# main_board_v2.net
KiCad netlist of a schematic drawn in EAGLE
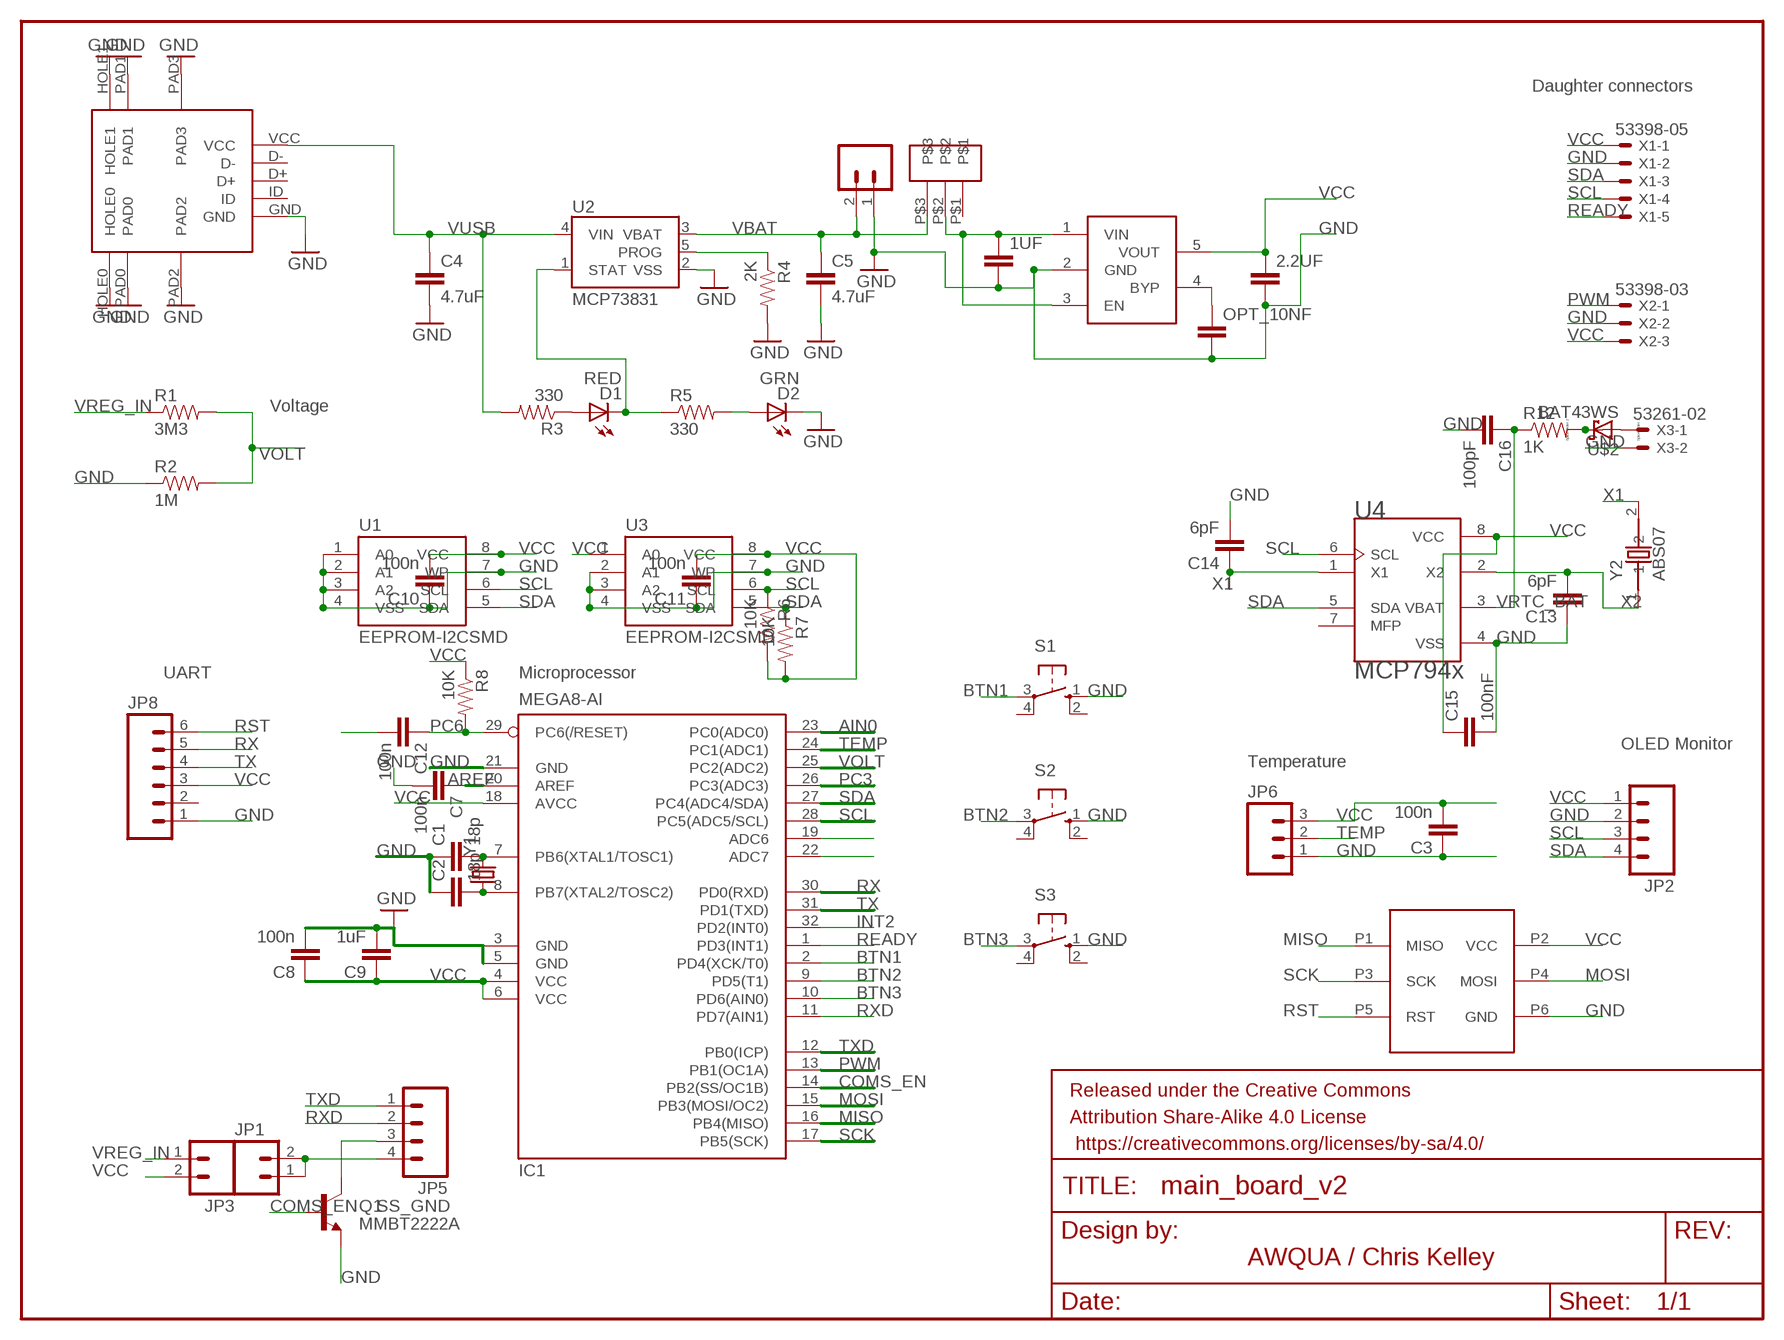
[diagram p0: schematic, sheet 1]

(export (version "E")
  (design (tool "Eeschema 10.0.6"))
  (components
    (comp (ref "1UF")
      (value "CAP0603-CAP")
      (footprint "eagle-import:0603-CAP")
      (libsource (lib "eagle-import") (part "SparkFun-Passives_CAP0603-CAP"))
    )
    (comp (ref "2.2UF")
      (value "CAP0603-CAP")
      (footprint "eagle-import:0603-CAP")
      (libsource (lib "eagle-import") (part "SparkFun-Passives_CAP0603-CAP"))
    )
    (comp (ref "C1")
      (value "18p")
      (footprint "eagle-import:0603-CAP")
      (libsource (lib "eagle-import") (part "CAP0603-CAP"))
    )
    (comp (ref "C2")
      (value "18p")
      (footprint "eagle-import:0603-CAP")
      (libsource (lib "eagle-import") (part "CAP0603-CAP"))
    )
    (comp (ref "C3")
      (value "100n")
      (footprint "eagle-import:0603-CAP")
      (libsource (lib "eagle-import") (part "CAP0603-CAP"))
    )
    (comp (ref "C4")
      (value "4.7uF")
      (footprint "eagle-import:0402-CAP")
      (libsource (lib "eagle-import") (part "CAP0402-CAP"))
    )
    (comp (ref "C5")
      (value "4.7uF")
      (footprint "eagle-import:0402-CAP")
      (libsource (lib "eagle-import") (part "CAP0402-CAP"))
    )
    (comp (ref "C7")
      (value "100n")
      (footprint "eagle-import:0603-CAP")
      (libsource (lib "eagle-import") (part "CAP0603-CAP"))
    )
    (comp (ref "C8")
      (value "100n")
      (footprint "eagle-import:0603-CAP")
      (libsource (lib "eagle-import") (part "CAP0603-CAP"))
    )
    (comp (ref "C9")
      (value "1uF")
      (footprint "eagle-import:0603-CAP")
      (libsource (lib "eagle-import") (part "CAP0603-CAP"))
    )
    (comp (ref "C10")
      (value "100n")
      (footprint "eagle-import:0603-CAP")
      (libsource (lib "eagle-import") (part "CAP0603-CAP"))
    )
    (comp (ref "C11")
      (value "100n")
      (footprint "eagle-import:0603-CAP")
      (libsource (lib "eagle-import") (part "CAP0603-CAP"))
    )
    (comp (ref "C12")
      (value "100n")
      (footprint "eagle-import:0603-CAP")
      (libsource (lib "eagle-import") (part "CAP0603-CAP"))
    )
    (comp (ref "C13")
      (value "6pF")
      (footprint "eagle-import:0603-CAP")
      (libsource (lib "eagle-import") (part "SparkFun-Passives_CAP0603-CAP"))
    )
    (comp (ref "C14")
      (value "6pF")
      (footprint "eagle-import:0603-CAP")
      (libsource (lib "eagle-import") (part "SparkFun-Passives_CAP0603-CAP"))
    )
    (comp (ref "C15")
      (value "100nF")
      (footprint "eagle-import:0603-CAP")
      (libsource (lib "eagle-import") (part "SparkFun-Passives_CAP0603-CAP"))
    )
    (comp (ref "C16")
      (value "100pF")
      (footprint "eagle-import:0603-CAP")
      (libsource (lib "eagle-import") (part "SparkFun-Passives_CAP0603-CAP"))
    )
    (comp (ref "D1")
      (value "RED")
      (footprint "eagle-import:LED-0603")
      (libsource (lib "eagle-import") (part "LED0603"))
    )
    (comp (ref "D2")
      (value "GRN")
      (footprint "eagle-import:LED-0603")
      (libsource (lib "eagle-import") (part "LED0603"))
    )
    (comp (ref "FRAME1")
      (value "FRAME-LETTER")
      (footprint "eagle-import:CREATIVE_COMMONS")
      (libsource (lib "eagle-import") (part "FRAME-LETTER"))
    )
    (comp (ref "IC1")
      (value "MEGA8-AI")
      (footprint "eagle-import:TQFP32-08")
      (fields (field (name "MPN") "ATMEGA8-16AU"))
      (libsource (lib "eagle-import") (part "MEGA8-AI"))
    )
    (comp (ref "JP1")
      (value "M02PTH")
      (footprint "eagle-import:1X02")
      (libsource (lib "eagle-import") (part "SparkFun-Connectors_M02PTH"))
    )
    (comp (ref "JP2")
      (value "M04PTH")
      (footprint "eagle-import:1X04")
      (libsource (lib "eagle-import") (part "M04PTH"))
    )
    (comp (ref "JP3")
      (value "M02PTH")
      (footprint "eagle-import:1X02")
      (libsource (lib "eagle-import") (part "SparkFun-Connectors_M02PTH"))
    )
    (comp (ref "JP5")
      (value "M04PTH")
      (footprint "eagle-import:1X04")
      (libsource (lib "eagle-import") (part "M04PTH"))
    )
    (comp (ref "JP6")
      (value "M03PTH")
      (footprint "eagle-import:1X03")
      (libsource (lib "eagle-import") (part "M03PTH"))
    )
    (comp (ref "JP7")
      (value "LiPo Battery")
      (footprint "eagle-import:JST-2-SMD")
      (libsource (lib "eagle-import") (part "M02-JST-2MM-SMT"))
    )
    (comp (ref "JP8")
      (value "M06SILK_FEMALE_PTH")
      (footprint "eagle-import:1X06")
      (libsource (lib "eagle-import") (part "M06SILK_FEMALE_PTH"))
    )
    (comp (ref "OPT_10NF")
      (value "CAP0603-CAP")
      (footprint "eagle-import:0603-CAP")
      (libsource (lib "eagle-import") (part "SparkFun-Passives_CAP0603-CAP"))
    )
    (comp (ref "Q1")
      (value "MMBT2222A")
      (footprint "eagle-import:SOT23-3")
      (libsource (lib "eagle-import") (part "TRANSISTOR_NPNMMBT2222A"))
    )
    (comp (ref "R1")
      (value "3M3")
      (footprint "eagle-import:0603-RES")
      (libsource (lib "eagle-import") (part "RESISTOR0603"))
    )
    (comp (ref "R2")
      (value "1M")
      (footprint "eagle-import:0603-RES")
      (libsource (lib "eagle-import") (part "RESISTOR0603"))
    )
    (comp (ref "R3")
      (value "330")
      (footprint "eagle-import:0402-RES")
      (libsource (lib "eagle-import") (part "RESISTOR0402-RES"))
    )
    (comp (ref "R4")
      (value "2K")
      (footprint "eagle-import:0402-RES")
      (libsource (lib "eagle-import") (part "RESISTOR0402-RES"))
    )
    (comp (ref "R5")
      (value "330")
      (footprint "eagle-import:0402-RES")
      (libsource (lib "eagle-import") (part "RESISTOR0402-RES"))
    )
    (comp (ref "R6")
      (value "10K")
      (footprint "eagle-import:0603-RES")
      (libsource (lib "eagle-import") (part "RESISTOR0603-RES"))
    )
    (comp (ref "R7")
      (value "10K")
      (footprint "eagle-import:0603-RES")
      (libsource (lib "eagle-import") (part "RESISTOR0603-RES"))
    )
    (comp (ref "R8")
      (value "10K")
      (footprint "eagle-import:0402-RES")
      (libsource (lib "eagle-import") (part "RESISTOR0402-RES"))
    )
    (comp (ref "R12")
      (value "1K")
      (footprint "eagle-import:0603-RES")
      (libsource (lib "eagle-import") (part "SparkFun-Passives_RESISTOR0603-RES"))
    )
    (comp (ref "S1")
      (value "40-XX")
      (footprint "eagle-import:B3F-40XX")
      (fields (field (name "MF") "OMRON COMPONENTS USA") (field (name "MPN") "B3F-4000"))
      (libsource (lib "eagle-import") (part "40-XX"))
    )
    (comp (ref "S2")
      (value "40-XX")
      (footprint "eagle-import:B3F-40XX")
      (fields (field (name "MF") "OMRON COMPONENTS USA") (field (name "MPN") "B3F-4000"))
      (libsource (lib "eagle-import") (part "40-XX"))
    )
    (comp (ref "S3")
      (value "40-XX")
      (footprint "eagle-import:B3F-40XX")
      (fields (field (name "MF") "OMRON COMPONENTS USA") (field (name "MPN") "B3F-4000"))
      (libsource (lib "eagle-import") (part "40-XX"))
    )
    (comp (ref "U$1")
      (value "ISP-SMD-6PIN")
      (footprint "eagle-import:ISP-SMD-6PIN")
      (libsource (lib "eagle-import") (part "ISP-SMD-6PIN"))
    )
    (comp (ref "U$2")
      (value "BAT43WS")
      (footprint "eagle-import:BAT43WS")
      (libsource (lib "eagle-import") (part "BAT43WS"))
    )
    (comp (ref "U$3")
      (value "USBMICRO-10118193-0001LF")
      (footprint "eagle-import:USBMICRO-10118193-0001LF")
      (libsource (lib "eagle-import") (part "USBMICRO-10118193-0001LF"))
    )
    (comp (ref "U$6")
      (value "LP2985")
      (footprint "eagle-import:LP2985")
      (libsource (lib "eagle-import") (part "LP2985"))
    )
    (comp (ref "U$7")
      (value "OS102-SPDT-SWITCH")
      (footprint "eagle-import:OS102-SPDT-SWITCH")
      (libsource (lib "eagle-import") (part "OS102-SPDT-SWITCH"))
    )
    (comp (ref "U1")
      (value "EEPROM-I2CSMD")
      (footprint "eagle-import:SO08")
      (libsource (lib "eagle-import") (part "EEPROM-I2CSMD"))
    )
    (comp (ref "U2")
      (value "MCP73831")
      (footprint "eagle-import:SOT23-5")
      (libsource (lib "eagle-import") (part "MCP73831"))
    )
    (comp (ref "U3")
      (value "EEPROM-I2CSMD")
      (footprint "eagle-import:SO08")
      (libsource (lib "eagle-import") (part "EEPROM-I2CSMD"))
    )
    (comp (ref "U4")
      (value "MCP794x")
      (footprint "eagle-import:SOIC127P600X175-8N")
      (fields (field (name "MF") "Microchip") (field (name "MP") "MCP7940M-I/SN"))
      (libsource (lib "eagle-import") (part "MCP7940M-I/SN"))
    )
    (comp (ref "X1")
      (value "53398-05")
      (footprint "eagle-import:53398-05")
      (libsource (lib "eagle-import") (part "53?-05398"))
    )
    (comp (ref "X2")
      (value "53398-03")
      (footprint "eagle-import:53398-03")
      (libsource (lib "eagle-import") (part "53?-03398"))
    )
    (comp (ref "X3")
      (value "53261-02")
      (footprint "eagle-import:53261-02")
      (libsource (lib "eagle-import") (part "53?-02261"))
    )
    (comp (ref "Y1")
      (value "CRYSTAL5X3")
      (footprint "eagle-import:CRYSTAL-SMD-5X3")
      (libsource (lib "eagle-import") (part "CRYSTAL5X3"))
    )
    (comp (ref "Y2")
      (value "ABS07")
      (footprint "eagle-import:XTAL320X150X90")
      (fields (field (name "MF") "Abracon") (field (name "MP") "ABS07-32.768KHZ-T"))
      (libsource (lib "eagle-import") (part "ABS07-32.768KHZ-T"))
    )
  )
  (nets
    (net (code "1") (name "/AIN0") (class "Default")
      (node (ref "IC1") (pin "23") (pinfunction "PC0(ADC0)_23") (pintype "bidirectional"))
    )
    (net (code "2") (name "/AREF") (class "Default")
      (node (ref "C7") (pin "1") (pinfunction "1_1") (pintype "passive"))
      (node (ref "IC1") (pin "20") (pinfunction "AREF_20") (pintype "passive"))
    )
    (net (code "3") (name "/BTN1") (class "Default")
      (node (ref "IC1") (pin "2") (pinfunction "PD4(XCK/T0)_2") (pintype "bidirectional"))
      (node (ref "S1") (pin "3") (pinfunction "P_3") (pintype "passive"))
    )
    (net (code "4") (name "/BTN2") (class "Default")
      (node (ref "IC1") (pin "9") (pinfunction "PD5(T1)_9") (pintype "bidirectional"))
      (node (ref "S2") (pin "3") (pinfunction "P_3") (pintype "passive"))
    )
    (net (code "5") (name "/BTN3") (class "Default")
      (node (ref "IC1") (pin "10") (pinfunction "PD6(AIN0)_10") (pintype "bidirectional"))
      (node (ref "S3") (pin "3") (pinfunction "P_3") (pintype "passive"))
    )
    (net (code "6") (name "/COMS_EN") (class "Default")
      (node (ref "IC1") (pin "14") (pinfunction "PB2(SS/OC1B)_14") (pintype "bidirectional"))
      (node (ref "Q1") (pin "1") (pinfunction "B_1") (pintype "passive"))
    )
    (net (code "7") (name "/INT2") (class "Default")
      (node (ref "IC1") (pin "32") (pinfunction "PD2(INT0)_32") (pintype "bidirectional"))
    )
    (net (code "8") (name "/MISO") (class "Default")
      (node (ref "IC1") (pin "16") (pinfunction "PB4(MISO)_16") (pintype "bidirectional"))
      (node (ref "U$1") (pin "P1") (pinfunction "MISO_P1") (pintype "bidirectional"))
    )
    (net (code "9") (name "/MOSI") (class "Default")
      (node (ref "IC1") (pin "15") (pinfunction "PB3(MOSI/OC2)_15") (pintype "bidirectional"))
      (node (ref "U$1") (pin "P4") (pinfunction "MOSI_P4") (pintype "bidirectional"))
    )
    (net (code "10") (name "/PC3") (class "Default")
      (node (ref "IC1") (pin "26") (pinfunction "PC3(ADC3)_26") (pintype "bidirectional"))
    )
    (net (code "11") (name "/PC6") (class "Default")
      (node (ref "C12") (pin "1") (pinfunction "1_1") (pintype "passive"))
      (node (ref "IC1") (pin "29") (pinfunction "PC6(/RESET)_29") (pintype "bidirectional"))
      (node (ref "R8") (pin "2") (pinfunction "2_2") (pintype "passive"))
    )
    (net (code "12") (name "/PWM") (class "Default")
      (node (ref "IC1") (pin "13") (pinfunction "PB1(OC1A)_13") (pintype "bidirectional"))
      (node (ref "X2") (pin "1") (pinfunction "S_1") (pintype "passive"))
    )
    (net (code "13") (name "/READY") (class "Default")
      (node (ref "IC1") (pin "1") (pinfunction "PD3(INT1)_1") (pintype "bidirectional"))
      (node (ref "X1") (pin "5") (pinfunction "S_5") (pintype "passive"))
    )
    (net (code "14") (name "/RST") (class "Default")
      (node (ref "C12") (pin "2") (pinfunction "2_2") (pintype "passive"))
      (node (ref "JP8") (pin "6") (pinfunction "6_6") (pintype "passive"))
      (node (ref "U$1") (pin "P5") (pinfunction "RST_P5") (pintype "bidirectional"))
    )
    (net (code "15") (name "/RX") (class "Default")
      (node (ref "IC1") (pin "30") (pinfunction "PD0(RXD)_30") (pintype "bidirectional"))
      (node (ref "JP8") (pin "5") (pinfunction "5_5") (pintype "passive"))
    )
    (net (code "16") (name "/RXD") (class "Default")
      (node (ref "IC1") (pin "11") (pinfunction "PD7(AIN1)_11") (pintype "bidirectional"))
      (node (ref "JP5") (pin "2") (pinfunction "2_2") (pintype "passive"))
    )
    (net (code "17") (name "/SCK") (class "Default")
      (node (ref "IC1") (pin "17") (pinfunction "PB5(SCK)_17") (pintype "bidirectional"))
      (node (ref "U$1") (pin "P3") (pinfunction "SCK_P3") (pintype "bidirectional"))
    )
    (net (code "18") (name "/SCL") (class "Default")
      (node (ref "IC1") (pin "28") (pinfunction "PC5(ADC5/SCL)_28") (pintype "bidirectional"))
      (node (ref "JP2") (pin "3") (pinfunction "3_3") (pintype "passive"))
      (node (ref "R6") (pin "1") (pinfunction "1_1") (pintype "passive"))
      (node (ref "U1") (pin "6") (pinfunction "SCL_6") (pintype "bidirectional"))
      (node (ref "U3") (pin "6") (pinfunction "SCL_6") (pintype "bidirectional"))
      (node (ref "U4") (pin "6") (pinfunction "SCL_6") (pintype "input"))
      (node (ref "X1") (pin "4") (pinfunction "S_4") (pintype "passive"))
    )
    (net (code "19") (name "/SDA") (class "Default")
      (node (ref "IC1") (pin "27") (pinfunction "PC4(ADC4/SDA)_27") (pintype "bidirectional"))
      (node (ref "JP2") (pin "4") (pinfunction "4_4") (pintype "passive"))
      (node (ref "R7") (pin "1") (pinfunction "1_1") (pintype "passive"))
      (node (ref "U1") (pin "5") (pinfunction "SDA_5") (pintype "bidirectional"))
      (node (ref "U3") (pin "5") (pinfunction "SDA_5") (pintype "bidirectional"))
      (node (ref "U4") (pin "5") (pinfunction "SDA_5") (pintype "bidirectional"))
      (node (ref "X1") (pin "3") (pinfunction "S_3") (pintype "passive"))
    )
    (net (code "20") (name "/SS_GND") (class "Default")
      (node (ref "JP5") (pin "3") (pinfunction "3_3") (pintype "passive"))
      (node (ref "Q1") (pin "3") (pinfunction "C_3") (pintype "passive"))
    )
    (net (code "21") (name "/TEMP") (class "Default")
      (node (ref "IC1") (pin "24") (pinfunction "PC1(ADC1)_24") (pintype "bidirectional"))
      (node (ref "JP6") (pin "2") (pinfunction "2_2") (pintype "passive"))
    )
    (net (code "22") (name "/TX") (class "Default")
      (node (ref "IC1") (pin "31") (pinfunction "PD1(TXD)_31") (pintype "bidirectional"))
      (node (ref "JP8") (pin "4") (pinfunction "4_4") (pintype "passive"))
    )
    (net (code "23") (name "/TXD") (class "Default")
      (node (ref "IC1") (pin "12") (pinfunction "PB0(ICP)_12") (pintype "bidirectional"))
      (node (ref "JP5") (pin "1") (pinfunction "1_1") (pintype "passive"))
    )
    (net (code "24") (name "/VBAT") (class "Default")
      (node (ref "C5") (pin "1") (pinfunction "1_1") (pintype "passive"))
      (node (ref "JP7") (pin "2") (pinfunction "2_2") (pintype "passive"))
      (node (ref "U$7") (pin "P$3") (pinfunction "P$3_P$3") (pintype "bidirectional"))
      (node (ref "U2") (pin "3") (pinfunction "VBAT_3") (pintype "power_in"))
    )
    (net (code "25") (name "/VCC") (class "Default")
      (node (ref "2.2UF") (pin "1") (pinfunction "1_1") (pintype "passive"))
      (node (ref "C10") (pin "2") (pinfunction "2_2") (pintype "passive"))
      (node (ref "C11") (pin "2") (pinfunction "2_2") (pintype "passive"))
      (node (ref "C15") (pin "1") (pinfunction "1_1") (pintype "passive"))
      (node (ref "C3") (pin "2") (pinfunction "2_2") (pintype "passive"))
      (node (ref "C8") (pin "1") (pinfunction "1_1") (pintype "passive"))
      (node (ref "C9") (pin "1") (pinfunction "1_1") (pintype "passive"))
      (node (ref "IC1") (pin "18") (pinfunction "AVCC_18") (pintype "power_in"))
      (node (ref "IC1") (pin "4") (pinfunction "VCC_4") (pintype "power_in"))
      (node (ref "IC1") (pin "6") (pinfunction "VCC_6") (pintype "power_in"))
      (node (ref "JP2") (pin "1") (pinfunction "1_1") (pintype "passive"))
      (node (ref "JP3") (pin "2") (pinfunction "2_2") (pintype "passive"))
      (node (ref "JP6") (pin "3") (pinfunction "3_3") (pintype "passive"))
      (node (ref "JP8") (pin "3") (pinfunction "3_3") (pintype "passive"))
      (node (ref "R6") (pin "2") (pinfunction "2_2") (pintype "passive"))
      (node (ref "R7") (pin "2") (pinfunction "2_2") (pintype "passive"))
      (node (ref "R8") (pin "1") (pinfunction "1_1") (pintype "passive"))
      (node (ref "U$1") (pin "P2") (pinfunction "VCC_P2") (pintype "bidirectional"))
      (node (ref "U$6") (pin "5") (pinfunction "VOUT_5") (pintype "bidirectional"))
      (node (ref "U1") (pin "8") (pinfunction "VCC_8") (pintype "power_in"))
      (node (ref "U3") (pin "1") (pinfunction "A0_1") (pintype "bidirectional"))
      (node (ref "U3") (pin "8") (pinfunction "VCC_8") (pintype "power_in"))
      (node (ref "U4") (pin "8") (pinfunction "VCC_8") (pintype "power_in"))
      (node (ref "X1") (pin "1") (pinfunction "S_1") (pintype "passive"))
      (node (ref "X2") (pin "3") (pinfunction "S_3") (pintype "passive"))
    )
    (net (code "26") (name "/VOLT") (class "Default")
      (node (ref "IC1") (pin "25") (pinfunction "PC2(ADC2)_25") (pintype "bidirectional"))
      (node (ref "R1") (pin "2") (pinfunction "2_2") (pintype "passive"))
      (node (ref "R2") (pin "2") (pinfunction "2_2") (pintype "passive"))
    )
    (net (code "27") (name "/VREG_IN") (class "Default")
      (node (ref "1UF") (pin "1") (pinfunction "1_1") (pintype "passive"))
      (node (ref "JP3") (pin "1") (pinfunction "1_1") (pintype "passive"))
      (node (ref "R1") (pin "1") (pinfunction "1_1") (pintype "passive"))
      (node (ref "U$6") (pin "1") (pinfunction "VIN_1") (pintype "bidirectional"))
      (node (ref "U$6") (pin "3") (pinfunction "EN_3") (pintype "bidirectional"))
      (node (ref "U$7") (pin "P$2") (pinfunction "P$2_P$2") (pintype "bidirectional"))
    )
    (net (code "28") (name "/VRTC_BAT") (class "Default")
      (node (ref "C16") (pin "1") (pinfunction "1_1") (pintype "passive"))
      (node (ref "R12") (pin "1") (pinfunction "1_1") (pintype "passive"))
      (node (ref "U4") (pin "3") (pinfunction "VBAT_3") (pintype "power_in"))
    )
    (net (code "29") (name "/VUSB") (class "Default")
      (node (ref "C4") (pin "1") (pinfunction "1_1") (pintype "passive"))
      (node (ref "R3") (pin "2") (pinfunction "2_2") (pintype "passive"))
      (node (ref "U$3") (pin "VCC") (pinfunction "VCC_VCC") (pintype "bidirectional"))
      (node (ref "U2") (pin "4") (pinfunction "VIN_4") (pintype "power_in"))
    )
    (net (code "30") (name "/X1") (class "Default")
      (node (ref "C14") (pin "1") (pinfunction "1_1") (pintype "passive"))
      (node (ref "U4") (pin "1") (pinfunction "X1_1") (pintype "input"))
      (node (ref "Y2") (pin "2") (pinfunction "2_2") (pintype "passive"))
    )
    (net (code "31") (name "/X2") (class "Default")
      (node (ref "C13") (pin "2") (pinfunction "2_2") (pintype "passive"))
      (node (ref "U4") (pin "2") (pinfunction "X2_2") (pintype "output"))
      (node (ref "Y2") (pin "1") (pinfunction "1_1") (pintype "passive"))
    )
    (net (code "32") (name "GND") (class "Default")
      (node (ref "1UF") (pin "2") (pinfunction "2_2") (pintype "passive"))
      (node (ref "2.2UF") (pin "2") (pinfunction "2_2") (pintype "passive"))
      (node (ref "C1") (pin "1") (pinfunction "1_1") (pintype "passive"))
      (node (ref "C10") (pin "1") (pinfunction "1_1") (pintype "passive"))
      (node (ref "C11") (pin "1") (pinfunction "1_1") (pintype "passive"))
      (node (ref "C13") (pin "1") (pinfunction "1_1") (pintype "passive"))
      (node (ref "C14") (pin "2") (pinfunction "2_2") (pintype "passive"))
      (node (ref "C15") (pin "2") (pinfunction "2_2") (pintype "passive"))
      (node (ref "C16") (pin "2") (pinfunction "2_2") (pintype "passive"))
      (node (ref "C2") (pin "1") (pinfunction "1_1") (pintype "passive"))
      (node (ref "C3") (pin "1") (pinfunction "1_1") (pintype "passive"))
      (node (ref "C4") (pin "2") (pinfunction "2_2") (pintype "passive"))
      (node (ref "C5") (pin "2") (pinfunction "2_2") (pintype "passive"))
      (node (ref "C7") (pin "2") (pinfunction "2_2") (pintype "passive"))
      (node (ref "C8") (pin "2") (pinfunction "2_2") (pintype "passive"))
      (node (ref "C9") (pin "2") (pinfunction "2_2") (pintype "passive"))
      (node (ref "D2") (pin "C") (pinfunction "C_C") (pintype "passive"))
      (node (ref "IC1") (pin "19") (pinfunction "ADC6_19") (pintype "bidirectional"))
      (node (ref "IC1") (pin "21") (pinfunction "GND_21") (pintype "power_in"))
      (node (ref "IC1") (pin "22") (pinfunction "ADC7_22") (pintype "bidirectional"))
      (node (ref "IC1") (pin "3") (pinfunction "GND_3") (pintype "power_in"))
      (node (ref "IC1") (pin "5") (pinfunction "GND_5") (pintype "power_in"))
      (node (ref "JP2") (pin "2") (pinfunction "2_2") (pintype "passive"))
      (node (ref "JP6") (pin "1") (pinfunction "1_1") (pintype "passive"))
      (node (ref "JP7") (pin "1") (pinfunction "1_1") (pintype "passive"))
      (node (ref "JP8") (pin "1") (pinfunction "1_1") (pintype "passive"))
      (node (ref "OPT_10NF") (pin "2") (pinfunction "2_2") (pintype "passive"))
      (node (ref "Q1") (pin "2") (pinfunction "E_2") (pintype "passive"))
      (node (ref "R2") (pin "1") (pinfunction "1_1") (pintype "passive"))
      (node (ref "R4") (pin "2") (pinfunction "2_2") (pintype "passive"))
      (node (ref "S1") (pin "1") (pinfunction "S_1") (pintype "passive"))
      (node (ref "S2") (pin "1") (pinfunction "S_1") (pintype "passive"))
      (node (ref "S3") (pin "1") (pinfunction "S_1") (pintype "passive"))
      (node (ref "U$1") (pin "P6") (pinfunction "GND_P6") (pintype "bidirectional"))
      (node (ref "U$3") (pin "GND") (pinfunction "GND_GND") (pintype "bidirectional"))
      (node (ref "U$3") (pin "HOLE0") (pinfunction "HOLE0_HOLE0") (pintype "bidirectional"))
      (node (ref "U$3") (pin "HOLE1") (pinfunction "HOLE1_HOLE1") (pintype "bidirectional"))
      (node (ref "U$3") (pin "PAD0") (pinfunction "PAD0_PAD0") (pintype "bidirectional"))
      (node (ref "U$3") (pin "PAD1") (pinfunction "PAD1_PAD1") (pintype "bidirectional"))
      (node (ref "U$3") (pin "PAD2") (pinfunction "PAD2_PAD2") (pintype "bidirectional"))
      (node (ref "U$3") (pin "PAD3") (pinfunction "PAD3_PAD3") (pintype "bidirectional"))
      (node (ref "U$6") (pin "2") (pinfunction "GND_2") (pintype "bidirectional"))
      (node (ref "U1") (pin "1") (pinfunction "A0_1") (pintype "bidirectional"))
      (node (ref "U1") (pin "2") (pinfunction "A1_2") (pintype "bidirectional"))
      (node (ref "U1") (pin "3") (pinfunction "A2_3") (pintype "bidirectional"))
      (node (ref "U1") (pin "4") (pinfunction "VSS_4") (pintype "power_in"))
      (node (ref "U1") (pin "7") (pinfunction "WP_7") (pintype "bidirectional"))
      (node (ref "U2") (pin "2") (pinfunction "VSS_2") (pintype "power_in"))
      (node (ref "U3") (pin "2") (pinfunction "A1_2") (pintype "bidirectional"))
      (node (ref "U3") (pin "3") (pinfunction "A2_3") (pintype "bidirectional"))
      (node (ref "U3") (pin "4") (pinfunction "VSS_4") (pintype "power_in"))
      (node (ref "U3") (pin "7") (pinfunction "WP_7") (pintype "bidirectional"))
      (node (ref "U4") (pin "4") (pinfunction "VSS_4") (pintype "passive"))
      (node (ref "X1") (pin "2") (pinfunction "S_2") (pintype "passive"))
      (node (ref "X2") (pin "2") (pinfunction "S_2") (pintype "passive"))
      (node (ref "X3") (pin "2") (pinfunction "S_2") (pintype "passive"))
    )
    (net (code "33") (name "Net-(D1-PadA)") (class "Default")
      (node (ref "D1") (pin "A") (pinfunction "A_A") (pintype "passive"))
      (node (ref "R3") (pin "1") (pinfunction "1_1") (pintype "passive"))
    )
    (net (code "34") (name "Net-(D2-PadA)") (class "Default")
      (node (ref "D2") (pin "A") (pinfunction "A_A") (pintype "passive"))
      (node (ref "R5") (pin "2") (pinfunction "2_2") (pintype "passive"))
    )
    (net (code "35") (name "Net-(IC1-PB6(XTAL1{slash}TOSC1))") (class "Default")
      (node (ref "C1") (pin "2") (pinfunction "2_2") (pintype "passive"))
      (node (ref "IC1") (pin "7") (pinfunction "PB6(XTAL1/TOSC1)_7") (pintype "bidirectional"))
      (node (ref "Y1") (pin "3") (pinfunction "2_3") (pintype "passive"))
    )
    (net (code "36") (name "Net-(IC1-PB7(XTAL2{slash}TOSC2))") (class "Default")
      (node (ref "C2") (pin "2") (pinfunction "2_2") (pintype "passive"))
      (node (ref "IC1") (pin "8") (pinfunction "PB7(XTAL2/TOSC2)_8") (pintype "bidirectional"))
      (node (ref "Y1") (pin "1") (pinfunction "1_1") (pintype "passive"))
    )
    (net (code "37") (name "Net-(JP1-Pad1)") (class "Default")
      (node (ref "JP1") (pin "1") (pinfunction "1_1") (pintype "passive"))
      (node (ref "JP1") (pin "2") (pinfunction "2_2") (pintype "passive"))
      (node (ref "JP5") (pin "4") (pinfunction "4_4") (pintype "passive"))
    )
    (net (code "38") (name "Net-(U$2-A)") (class "Default")
      (node (ref "R12") (pin "2") (pinfunction "2_2") (pintype "passive"))
      (node (ref "U$2") (pin "PIN2") (pinfunction "A_PIN2") (pintype "passive"))
    )
    (net (code "39") (name "Net-(U$2-C)") (class "Default")
      (node (ref "U$2") (pin "PIN1") (pinfunction "C_PIN1") (pintype "passive"))
      (node (ref "X3") (pin "1") (pinfunction "S_1") (pintype "passive"))
    )
    (net (code "40") (name "Net-(U$6-BYP)") (class "Default")
      (node (ref "OPT_10NF") (pin "1") (pinfunction "1_1") (pintype "passive"))
      (node (ref "U$6") (pin "4") (pinfunction "BYP_4") (pintype "bidirectional"))
    )
    (net (code "41") (name "Net-(U2-PROG)") (class "Default")
      (node (ref "R4") (pin "1") (pinfunction "1_1") (pintype "passive"))
      (node (ref "U2") (pin "5") (pinfunction "PROG_5") (pintype "input"))
    )
    (net (code "42") (name "Net-(U2-STAT)") (class "Default")
      (node (ref "D1") (pin "C") (pinfunction "C_C") (pintype "passive"))
      (node (ref "R5") (pin "1") (pinfunction "1_1") (pintype "passive"))
      (node (ref "U2") (pin "1") (pinfunction "STAT_1") (pintype "output"))
    )
    (net (code "43") (name "unconnected-(JP8-Pad2)") (class "Default")
      (node (ref "JP8") (pin "2") (pinfunction "2_2") (pintype "passive"))
    )
    (net (code "44") (name "unconnected-(S1-P1-Pad4)") (class "Default")
      (node (ref "S1") (pin "4") (pinfunction "P1_4") (pintype "passive"))
    )
    (net (code "45") (name "unconnected-(S1-S1-Pad2)") (class "Default")
      (node (ref "S1") (pin "2") (pinfunction "S1_2") (pintype "passive"))
    )
    (net (code "46") (name "unconnected-(S2-P1-Pad4)") (class "Default")
      (node (ref "S2") (pin "4") (pinfunction "P1_4") (pintype "passive"))
    )
    (net (code "47") (name "unconnected-(S2-S1-Pad2)") (class "Default")
      (node (ref "S2") (pin "2") (pinfunction "S1_2") (pintype "passive"))
    )
    (net (code "48") (name "unconnected-(S3-P1-Pad4)") (class "Default")
      (node (ref "S3") (pin "4") (pinfunction "P1_4") (pintype "passive"))
    )
    (net (code "49") (name "unconnected-(S3-S1-Pad2)") (class "Default")
      (node (ref "S3") (pin "2") (pinfunction "S1_2") (pintype "passive"))
    )
    (net (code "50") (name "unconnected-(U$3-PadD+)") (class "Default")
      (node (ref "U$3") (pin "D+") (pinfunction "D+_D+") (pintype "bidirectional"))
    )
    (net (code "51") (name "unconnected-(U$3-PadD-)") (class "Default")
      (node (ref "U$3") (pin "D-") (pinfunction "D-_D-") (pintype "bidirectional"))
    )
    (net (code "52") (name "unconnected-(U$3-PadID)") (class "Default")
      (node (ref "U$3") (pin "ID") (pinfunction "ID_ID") (pintype "bidirectional"))
    )
    (net (code "53") (name "unconnected-(U$7-PadP$1)") (class "Default")
      (node (ref "U$7") (pin "P$1") (pinfunction "P$1_P$1") (pintype "bidirectional"))
    )
    (net (code "54") (name "unconnected-(U4-MFP-Pad7)") (class "Default")
      (node (ref "U4") (pin "7") (pinfunction "MFP_7") (pintype "bidirectional"))
    )
  )
)
